# Adafruit_LSM303DLHC.net
KiCad netlist of a schematic drawn in EAGLE
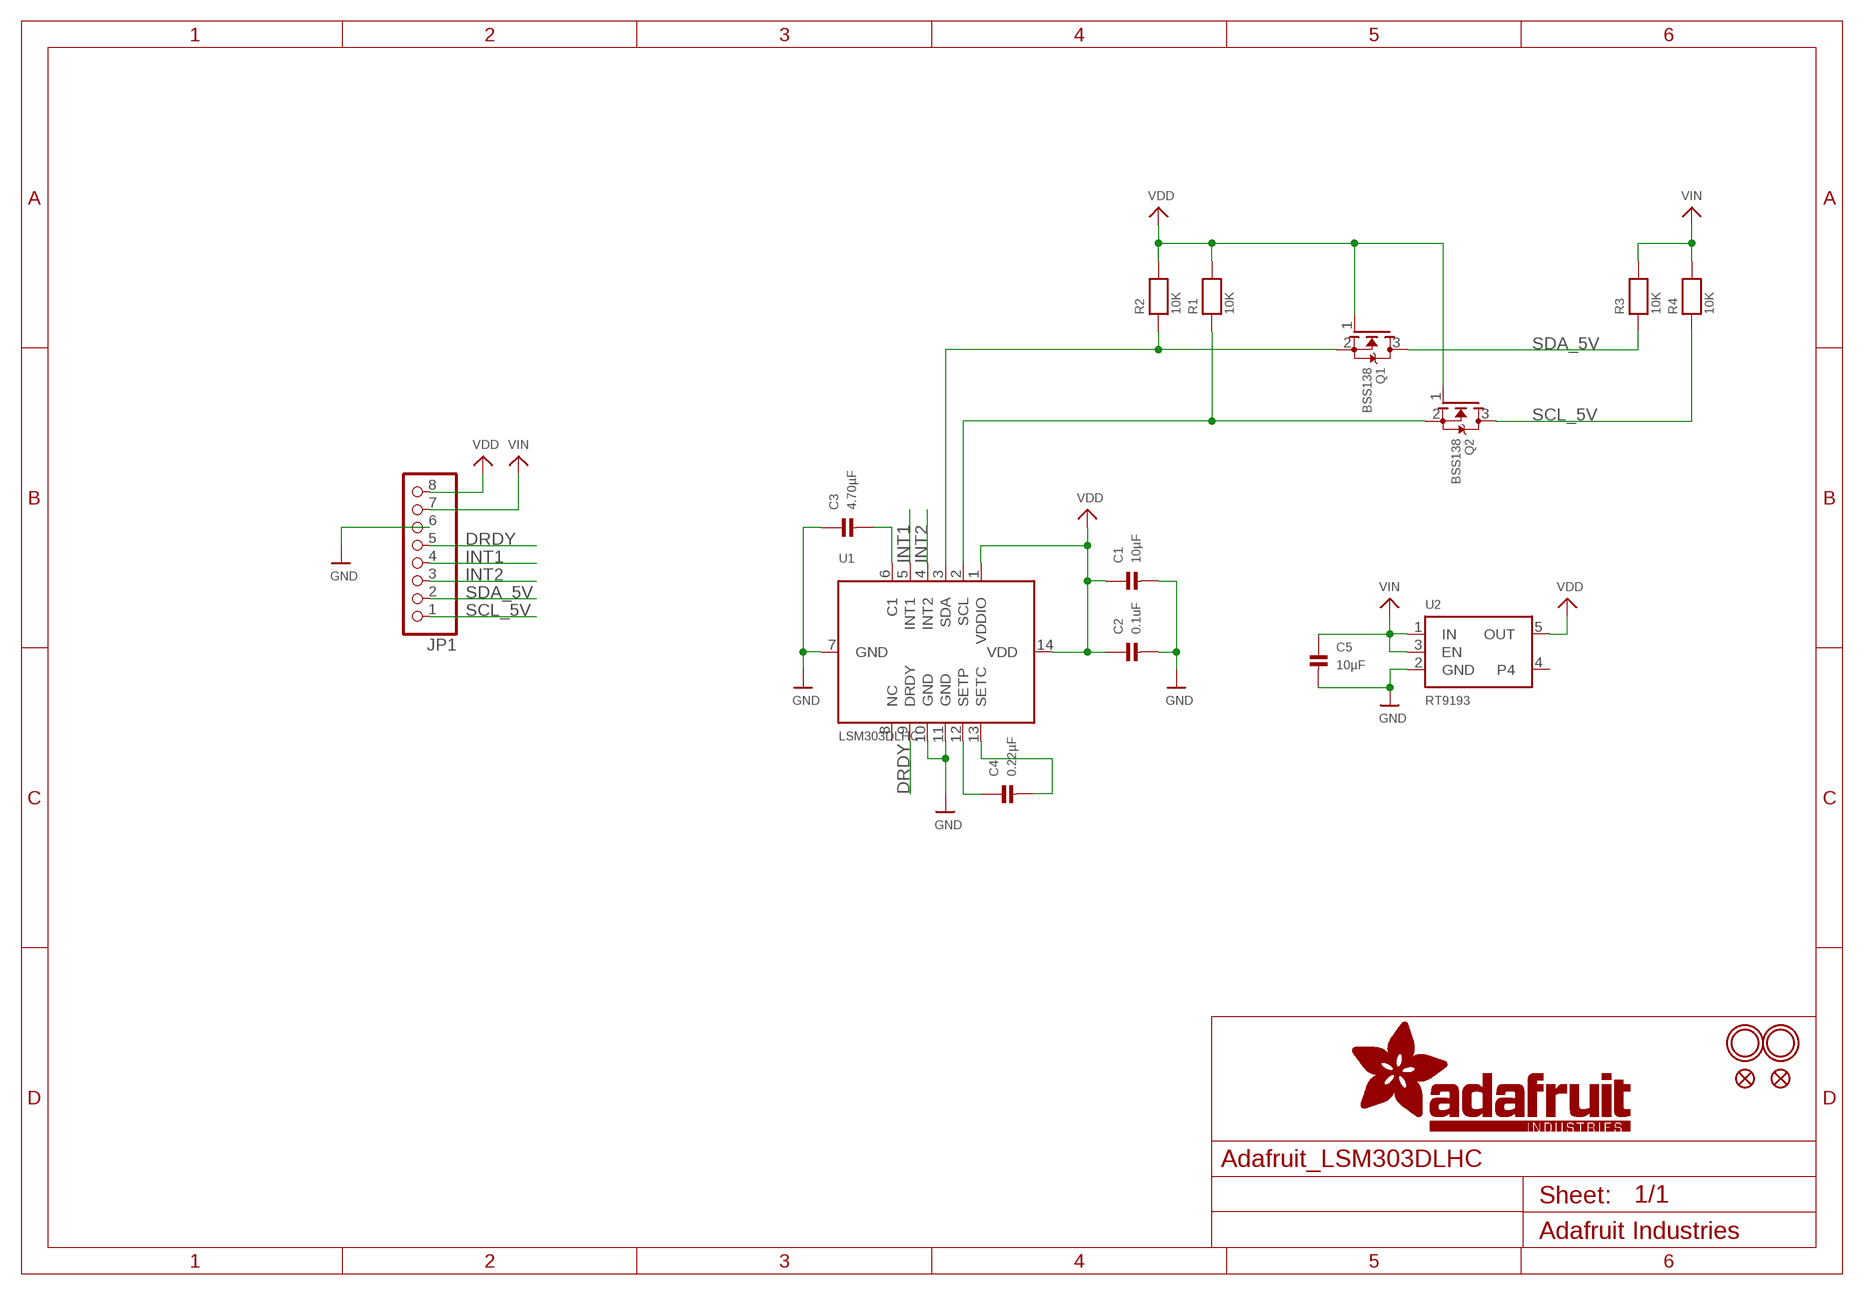
[diagram p0: schematic, sheet 1]

(export (version "E")
  (design (tool "Eeschema 10.0.6"))
  (components
    (comp (ref "C1")
      (value "10µF")
      (footprint "eagle-import:_0805")
      (libsource (lib "eagle-import") (part "CAP_CERAMIC_0805"))
    )
    (comp (ref "C2")
      (value "0.1uF")
      (footprint "eagle-import:_0805")
      (libsource (lib "eagle-import") (part "CAP_CERAMIC_0805"))
    )
    (comp (ref "C3")
      (value "4.70µF")
      (footprint "eagle-import:_0805")
      (libsource (lib "eagle-import") (part "CAP_CERAMIC_0805"))
    )
    (comp (ref "C4")
      (value "0.22µF")
      (footprint "eagle-import:_0805")
      (libsource (lib "eagle-import") (part "CAP_CERAMIC_0805"))
    )
    (comp (ref "C5")
      (value "10µF")
      (footprint "eagle-import:_0805")
      (libsource (lib "eagle-import") (part "CAP_CERAMIC_0805"))
    )
    (comp (ref "FID1")
      (value "FIDUCIAL\"\"")
      (footprint "eagle-import:FIDUCIAL_1MM")
      (libsource (lib "eagle-import") (part "FIDUCIAL{dblquote}{dblquote}"))
    )
    (comp (ref "FID2")
      (value "FIDUCIAL\"\"")
      (footprint "eagle-import:FIDUCIAL_1MM")
      (libsource (lib "eagle-import") (part "FIDUCIAL{dblquote}{dblquote}"))
    )
    (comp (ref "JP1")
      (value "HEADER-1X876MIL")
      (footprint "eagle-import:1X08_ROUND_76")
      (libsource (lib "eagle-import") (part "HEADER-1X876MIL"))
    )
    (comp (ref "Q1")
      (value "BSS138")
      (footprint "eagle-import:SOT23-WIDE")
      (libsource (lib "eagle-import") (part "MOSFET-NWIDE"))
    )
    (comp (ref "Q2")
      (value "BSS138")
      (footprint "eagle-import:SOT23-WIDE")
      (libsource (lib "eagle-import") (part "MOSFET-NWIDE"))
    )
    (comp (ref "R1")
      (value "10K")
      (footprint "eagle-import:_0805")
      (libsource (lib "eagle-import") (part "RESISTOR_0805"))
    )
    (comp (ref "R2")
      (value "10K")
      (footprint "eagle-import:_0805")
      (libsource (lib "eagle-import") (part "RESISTOR_0805"))
    )
    (comp (ref "R3")
      (value "10K")
      (footprint "eagle-import:_0805")
      (libsource (lib "eagle-import") (part "RESISTOR_0805"))
    )
    (comp (ref "R4")
      (value "10K")
      (footprint "eagle-import:_0805")
      (libsource (lib "eagle-import") (part "RESISTOR_0805"))
    )
    (comp (ref "U$3")
      (value "MOUNTINGHOLE2.5")
      (footprint "eagle-import:MOUNTINGHOLE_2.5_PLATED")
      (libsource (lib "eagle-import") (part "MOUNTINGHOLE2.5"))
    )
    (comp (ref "U$4")
      (value "MOUNTINGHOLE2.5")
      (footprint "eagle-import:MOUNTINGHOLE_2.5_PLATED")
      (libsource (lib "eagle-import") (part "MOUNTINGHOLE2.5"))
    )
    (comp (ref "U1")
      (value "LSM303DLHC")
      (footprint "eagle-import:LGA14")
      (libsource (lib "eagle-import") (part "LSM303DLHC"))
    )
    (comp (ref "U2")
      (value "RT9193")
      (footprint "eagle-import:SOT23-5")
      (libsource (lib "eagle-import") (part "VREG_SOT23-5"))
    )
  )
  (nets
    (net (code "1") (name "/DRDY") (class "Default")
      (node (ref "JP1") (pin "5") (pinfunction "5_5") (pintype "passive"))
      (node (ref "U1") (pin "9") (pinfunction "DRDY_9") (pintype "output"))
    )
    (net (code "2") (name "/INT1") (class "Default")
      (node (ref "JP1") (pin "4") (pinfunction "4_4") (pintype "passive"))
      (node (ref "U1") (pin "5") (pinfunction "INT1_5") (pintype "output"))
    )
    (net (code "3") (name "/INT2") (class "Default")
      (node (ref "JP1") (pin "3") (pinfunction "3_3") (pintype "passive"))
      (node (ref "U1") (pin "4") (pinfunction "INT2_4") (pintype "output"))
    )
    (net (code "4") (name "/SCL_5V") (class "Default")
      (node (ref "JP1") (pin "1") (pinfunction "1_1") (pintype "passive"))
      (node (ref "Q2") (pin "3") (pinfunction "D_3") (pintype "bidirectional"))
      (node (ref "R4") (pin "1") (pinfunction "1_1") (pintype "passive"))
    )
    (net (code "5") (name "/SDA_5V") (class "Default")
      (node (ref "JP1") (pin "2") (pinfunction "2_2") (pintype "passive"))
      (node (ref "Q1") (pin "3") (pinfunction "D_3") (pintype "bidirectional"))
      (node (ref "R3") (pin "1") (pinfunction "1_1") (pintype "passive"))
    )
    (net (code "6") (name "GND") (class "Default")
      (node (ref "C1") (pin "2") (pinfunction "P$2_2") (pintype "passive"))
      (node (ref "C2") (pin "2") (pinfunction "P$2_2") (pintype "passive"))
      (node (ref "C3") (pin "1") (pinfunction "P$1_1") (pintype "passive"))
      (node (ref "C5") (pin "2") (pinfunction "P$2_2") (pintype "passive"))
      (node (ref "JP1") (pin "6") (pinfunction "6_6") (pintype "passive"))
      (node (ref "U1") (pin "10") (pinfunction "GND_10") (pintype "power_in"))
      (node (ref "U1") (pin "11") (pinfunction "GND_11") (pintype "power_in"))
      (node (ref "U1") (pin "7") (pinfunction "GND_7") (pintype "power_in"))
      (node (ref "U2") (pin "2") (pinfunction "GND_2") (pintype "bidirectional"))
    )
    (net (code "7") (name "Net-(C3-P$2)") (class "Default")
      (node (ref "C3") (pin "2") (pinfunction "P$2_2") (pintype "passive"))
      (node (ref "U1") (pin "6") (pinfunction "C1_6") (pintype "bidirectional"))
    )
    (net (code "8") (name "Net-(C4-P$1)") (class "Default")
      (node (ref "C4") (pin "1") (pinfunction "P$1_1") (pintype "passive"))
      (node (ref "U1") (pin "12") (pinfunction "SETP_12") (pintype "bidirectional"))
    )
    (net (code "9") (name "Net-(C4-P$2)") (class "Default")
      (node (ref "C4") (pin "2") (pinfunction "P$2_2") (pintype "passive"))
      (node (ref "U1") (pin "13") (pinfunction "SETC_13") (pintype "bidirectional"))
    )
    (net (code "10") (name "Net-(Q1-S)") (class "Default")
      (node (ref "Q1") (pin "2") (pinfunction "S_2") (pintype "bidirectional"))
      (node (ref "R2") (pin "1") (pinfunction "1_1") (pintype "passive"))
      (node (ref "U1") (pin "3") (pinfunction "SDA_3") (pintype "bidirectional"))
    )
    (net (code "11") (name "Net-(Q2-S)") (class "Default")
      (node (ref "Q2") (pin "2") (pinfunction "S_2") (pintype "bidirectional"))
      (node (ref "R1") (pin "1") (pinfunction "1_1") (pintype "passive"))
      (node (ref "U1") (pin "2") (pinfunction "SCL_2") (pintype "bidirectional"))
    )
    (net (code "12") (name "VDD") (class "Default")
      (node (ref "C1") (pin "1") (pinfunction "P$1_1") (pintype "passive"))
      (node (ref "C2") (pin "1") (pinfunction "P$1_1") (pintype "passive"))
      (node (ref "JP1") (pin "8") (pinfunction "8_8") (pintype "passive"))
      (node (ref "Q1") (pin "1") (pinfunction "G_1") (pintype "bidirectional"))
      (node (ref "Q2") (pin "1") (pinfunction "G_1") (pintype "bidirectional"))
      (node (ref "R1") (pin "2") (pinfunction "2_2") (pintype "passive"))
      (node (ref "R2") (pin "2") (pinfunction "2_2") (pintype "passive"))
      (node (ref "U1") (pin "1") (pinfunction "VDDIO_1") (pintype "power_in"))
      (node (ref "U1") (pin "14") (pinfunction "VDD_14") (pintype "power_in"))
      (node (ref "U2") (pin "5") (pinfunction "OUT_5") (pintype "bidirectional"))
    )
    (net (code "13") (name "VIN") (class "Default")
      (node (ref "C5") (pin "1") (pinfunction "P$1_1") (pintype "passive"))
      (node (ref "JP1") (pin "7") (pinfunction "7_7") (pintype "passive"))
      (node (ref "R3") (pin "2") (pinfunction "2_2") (pintype "passive"))
      (node (ref "R4") (pin "2") (pinfunction "2_2") (pintype "passive"))
      (node (ref "U2") (pin "1") (pinfunction "IN_1") (pintype "bidirectional"))
      (node (ref "U2") (pin "3") (pinfunction "EN_3") (pintype "bidirectional"))
    )
    (net (code "14") (name "unconnected-(U1-NC-Pad8)") (class "Default")
      (node (ref "U1") (pin "8") (pinfunction "NC_8") (pintype "bidirectional"))
    )
    (net (code "15") (name "unconnected-(U2-P4-Pad4)") (class "Default")
      (node (ref "U2") (pin "4") (pinfunction "P4_4") (pintype "bidirectional"))
    )
  )
)
